# Power.net
KiCad netlist of a schematic drawn in Altium Designer
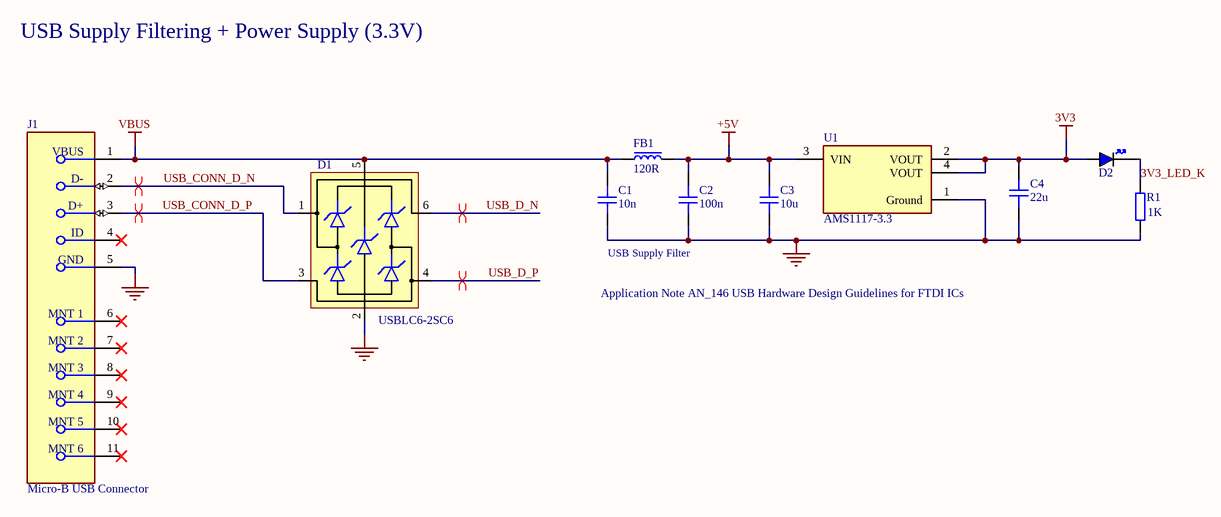
[diagram p0: Power.SchDoc]

(export (version "E")
  (design (tool "Eeschema 10.0.6"))
  (components
    (comp (ref "C1")
      (value "10n")
      (footprint "CAP_0603")
      (description "Capacitor SMD 0603")
      (libsource (lib "Schematic-Lib-PhilsLab") (part "CAP_0603"))
    )
    (comp (ref "C2")
      (value "100n")
      (footprint "CAP_0603")
      (description "Capacitor SMD 0603")
      (libsource (lib "Schematic-Lib-PhilsLab") (part "CAP_0603"))
    )
    (comp (ref "C3")
      (value "10u")
      (footprint "CAP_0603")
      (description "Capacitor SMD 0603")
      (libsource (lib "Schematic-Lib-PhilsLab") (part "CAP_0603"))
    )
    (comp (ref "C4")
      (value "22u")
      (footprint "CAP_0603")
      (description "Capacitor SMD 0603")
      (libsource (lib "Schematic-Lib-PhilsLab") (part "CAP_0603"))
    )
    (comp (ref "D1")
      (value "USBLC6-2SC6")
      (footprint "SOT-23-6")
      (description "Low-Capacitance ESD Protection USB")
      (fields (field (name "MANUFACTURER") "STMicroelectronics"))
      (libsource (lib "Schematic-Lib-PhilsLab") (part "USBLC6-2SC6"))
    )
    (comp (ref "D2")
      (value "BLUE")
      (footprint "LED_0402_BLUE")
      (description "LED 0402 BLUE SMD")
      (libsource (lib "Schematic-Lib-PhilsLab") (part "LED_0402_BLUE"))
    )
    (comp (ref "FB1")
      (value "120R")
      (footprint "FB_0603")
      (description "Ferrite Bead SMD 0603")
      (libsource (lib "Schematic-Lib-PhilsLab") (part "FB_0603"))
    )
    (comp (ref "J1")
      (value "Micro-B USB Connector")
      (footprint "FP-473460001-MFG")
      (description "CONN RCPT USB2.0 MICRO B SMD R/A")
      (fields
        (field (name "OCTOPART") "https://octopart.com/47346-0001-molex-7164928")
        (field (name "MANUFACTURER") "Molex")
      )
      (libsource (lib "Altium Content Vault") (part "53ae1f1d9b557310b43ca686e5bb76a"))
    )
    (comp (ref "R1")
      (value "1K")
      (footprint "RES_0402")
      (description "Resistor SMD 0402")
      (libsource (lib "Schematic-Lib-PhilsLab") (part "RES_0402"))
    )
    (comp (ref "U1")
      (value "AMS1117-3.3")
      (footprint "FP-AMS1117-IPC_C")
      (description "LDO Voltage Regulators 1A, 3.3V")
      (fields
        (field (name "OCTOPART") "https://octopart.com/ams1117-3.3-advanced+monolithic+systems-25899300")
        (field (name "MANUFACTURER") "Advanced Monolithic Systems")
      )
      (libsource (lib "Altium Content Vault") (part "8bdbb5f8e77002000e30dd2845d0354"))
    )
  )
  (nets
    (net (code "1") (name "+5V") (class "Default")
      (node (ref "C2") (pin "2") (pinfunction "2_2") (pintype "passive"))
      (node (ref "C3") (pin "2") (pinfunction "2_2") (pintype "passive"))
      (node (ref "FB1") (pin "2") (pinfunction "2_2") (pintype "passive"))
      (node (ref "U1") (pin "3") (pinfunction "VIN_3") (pintype "power_in"))
    )
    (net (code "2") (name "/3V3_LED_K") (class "Default")
      (node (ref "D2") (pin "K") (pinfunction "K_K") (pintype "passive"))
      (node (ref "R1") (pin "1") (pinfunction "1_1") (pintype "passive"))
    )
    (net (code "3") (name "/USB_CONN_D_N") (class "Default")
      (node (ref "D1") (pin "1") (pinfunction "IO1_1") (pintype "bidirectional"))
      (node (ref "J1") (pin "2") (pinfunction "D-_2") (pintype "bidirectional"))
    )
    (net (code "4") (name "/USB_CONN_D_P") (class "Default")
      (node (ref "D1") (pin "3") (pinfunction "IO2_3") (pintype "bidirectional"))
      (node (ref "J1") (pin "3") (pinfunction "D+_3") (pintype "bidirectional"))
    )
    (net (code "5") (name "/USB_D_N") (class "Default")
      (node (ref "D1") (pin "6") (pinfunction "IO1_6") (pintype "bidirectional"))
    )
    (net (code "6") (name "/USB_D_P") (class "Default")
      (node (ref "D1") (pin "4") (pinfunction "IO2_4") (pintype "bidirectional"))
    )
    (net (code "7") (name "3V3") (class "Default")
      (node (ref "C4") (pin "2") (pinfunction "2_2") (pintype "passive"))
      (node (ref "D2") (pin "A") (pinfunction "A_A") (pintype "passive"))
      (node (ref "U1") (pin "2") (pinfunction "VOUT_2") (pintype "passive"))
      (node (ref "U1") (pin "4") (pinfunction "VOUT_4") (pintype "passive"))
    )
    (net (code "8") (name "GND") (class "Default")
      (node (ref "C1") (pin "1") (pinfunction "1_1") (pintype "passive"))
      (node (ref "C2") (pin "1") (pinfunction "1_1") (pintype "passive"))
      (node (ref "C3") (pin "1") (pinfunction "1_1") (pintype "passive"))
      (node (ref "C4") (pin "1") (pinfunction "1_1") (pintype "passive"))
      (node (ref "D1") (pin "2") (pinfunction "GND_2") (pintype "power_in"))
      (node (ref "J1") (pin "5") (pinfunction "GND_5") (pintype "power_in"))
      (node (ref "R1") (pin "2") (pinfunction "2_2") (pintype "passive"))
      (node (ref "U1") (pin "1") (pinfunction "Ground_1") (pintype "power_in"))
    )
    (net (code "9") (name "VBUS") (class "Default")
      (node (ref "C1") (pin "2") (pinfunction "2_2") (pintype "passive"))
      (node (ref "D1") (pin "5") (pinfunction "VBUS_5") (pintype "power_in"))
      (node (ref "FB1") (pin "1") (pinfunction "1_1") (pintype "passive"))
      (node (ref "J1") (pin "1") (pinfunction "VBUS_1") (pintype "power_in"))
    )
    (net (code "10") (name "unconnected-(J1-ID-Pad4)") (class "Default")
      (node (ref "J1") (pin "4") (pinfunction "ID_4") (pintype "passive+no_connect"))
    )
    (net (code "11") (name "unconnected-(J1-MNT_1-Pad6)") (class "Default")
      (node (ref "J1") (pin "6") (pinfunction "MNT_1_6") (pintype "passive+no_connect"))
    )
    (net (code "12") (name "unconnected-(J1-MNT_2-Pad7)") (class "Default")
      (node (ref "J1") (pin "7") (pinfunction "MNT_2_7") (pintype "passive+no_connect"))
    )
    (net (code "13") (name "unconnected-(J1-MNT_3-Pad8)") (class "Default")
      (node (ref "J1") (pin "8") (pinfunction "MNT_3_8") (pintype "passive+no_connect"))
    )
    (net (code "14") (name "unconnected-(J1-MNT_4-Pad9)") (class "Default")
      (node (ref "J1") (pin "9") (pinfunction "MNT_4_9") (pintype "passive+no_connect"))
    )
    (net (code "15") (name "unconnected-(J1-MNT_5-Pad10)") (class "Default")
      (node (ref "J1") (pin "10") (pinfunction "MNT_5_10") (pintype "passive+no_connect"))
    )
    (net (code "16") (name "unconnected-(J1-MNT_6-Pad11)") (class "Default")
      (node (ref "J1") (pin "11") (pinfunction "MNT_6_11") (pintype "passive+no_connect"))
    )
  )
)
